# Mainboard_Geneva_Interface.net
KiCad netlist of a schematic drawn in Altium Designer
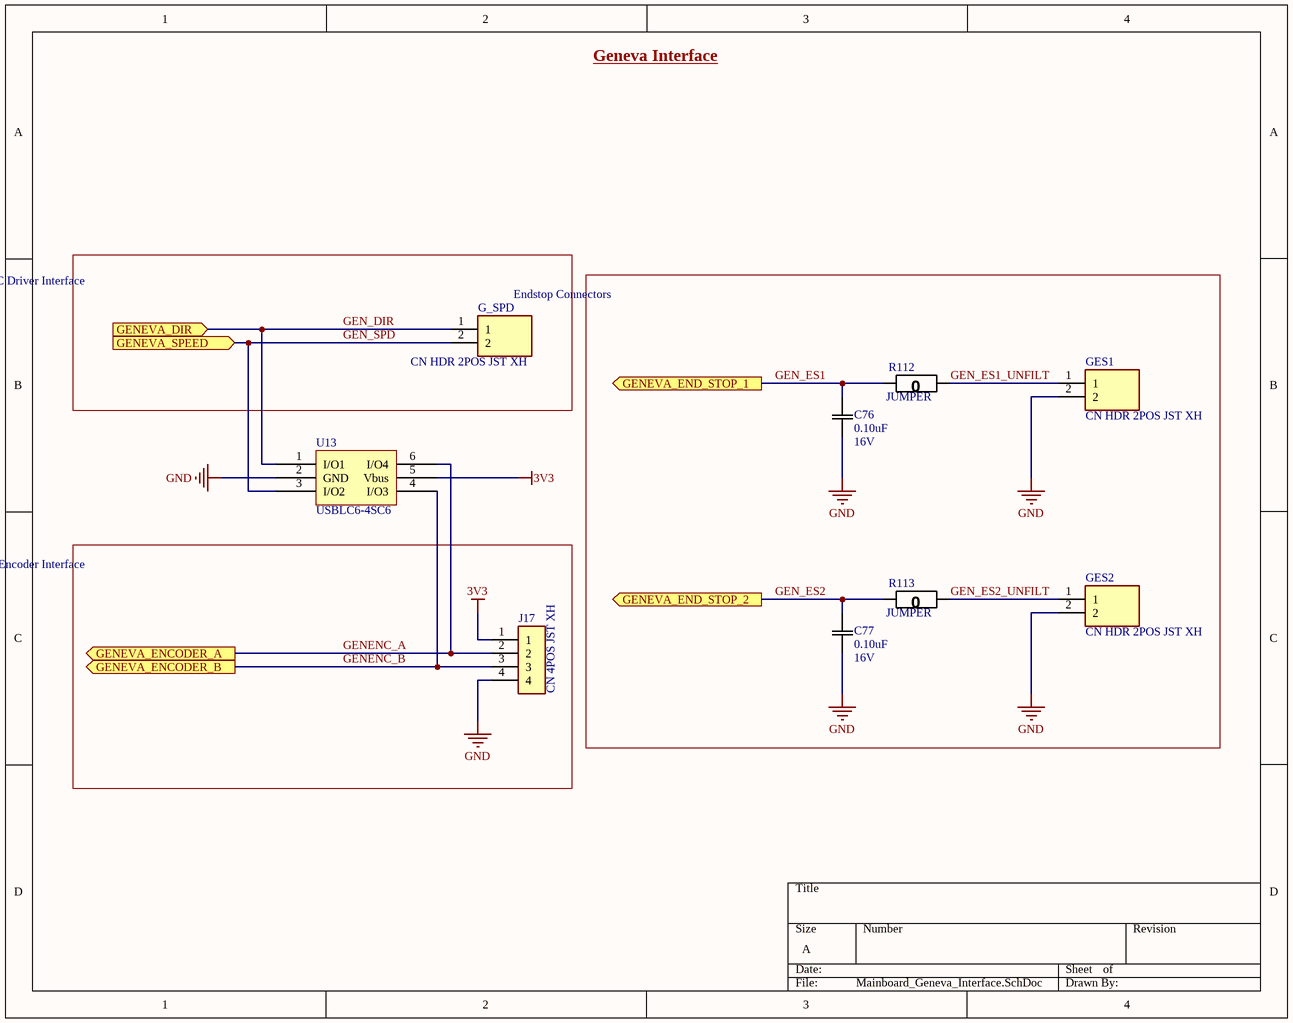
[diagram p0: Mainboard_Geneva_Interface.SchDoc]

(export (version "E")
  (design (tool "Eeschema 10.0.6"))
  (components
    (comp (ref "C76")
      (value "0.10uF")
      (footprint "0603")
      (description "CAP CER 0.10UF 16V X5R 0603/0805")
      (fields (field (name "TOLERANCE") "10%") (field (name "RATING") "16V"))
      (libsource (lib "AltiumLibraries") (part "CAP 0.10uF 16V"))
    )
    (comp (ref "C77")
      (value "0.10uF")
      (footprint "0603")
      (description "CAP CER 0.10UF 16V X5R 0603/0805")
      (fields (field (name "TOLERANCE") "10%") (field (name "RATING") "16V"))
      (libsource (lib "AltiumLibraries") (part "CAP 0.10uF 16V"))
    )
    (comp (ref "GES1")
      (value "CN HDR 2POS JST XH")
      (footprint "JST_B2B-XH-A(LF)(SN)")
      (description "Connector Header Through Hole 2 position 0.098 _2.50mm_\r\nJST XH")
      (fields (field (name "MP") "B2B-XH-A_LF__SN_") (field (name "MF") "JST Sales"))
      (libsource (lib "AltiumLibraries") (part "CN HDR 2POS JST XH"))
    )
    (comp (ref "GES2")
      (value "CN HDR 2POS JST XH")
      (footprint "JST_B2B-XH-A(LF)(SN)")
      (description "Connector Header Through Hole 2 position 0.098 _2.50mm_\r\nJST XH")
      (fields (field (name "MP") "B2B-XH-A_LF__SN_") (field (name "MF") "JST Sales"))
      (libsource (lib "AltiumLibraries") (part "CN HDR 2POS JST XH"))
    )
    (comp (ref "G_SPD")
      (value "CN HDR 2POS JST XH")
      (footprint "JST_B2B-XH-A(LF)(SN)")
      (description "Connector Header Through Hole 2 position 0.098 _2.50mm_\r\nJST XH")
      (fields (field (name "MP") "B2B-XH-A_LF__SN_") (field (name "MF") "JST Sales"))
      (libsource (lib "AltiumLibraries") (part "CN HDR 2POS JST XH"))
    )
    (comp (ref "J17")
      (value "CN 4POS JST XH")
      (footprint "JST_B4B-XH-A(LF)(SN)")
      (description "Connector Header Through Hole 4 position 0.098 _2.50mm_\r\nB4B-XH-A(LF)(SN)")
      (fields (field (name "MP") "B4B-XH-A_LF__SN_") (field (name "MF") "JST Sales"))
      (libsource (lib "AltiumLibraries") (part "CN 4POS JST XH"))
    )
    (comp (ref "R112")
      (value "JUMPER")
      (footprint "0603")
      (description "RES SMD 0 OHM JUMPER GENERIC 0805")
      (libsource (lib "AltiumLibraries") (part "RES 0 JUMPER"))
    )
    (comp (ref "R113")
      (value "JUMPER")
      (footprint "0603")
      (description "RES SMD 0 OHM JUMPER GENERIC 0805")
      (libsource (lib "AltiumLibraries") (part "RES 0 JUMPER"))
    )
    (comp (ref "U13")
      (value "USBLC6-4SC6")
      (footprint "SOT23-6L")
      (libsource (lib "AltiumLibraries") (part "USBLC6-4SC6"))
    )
  )
  (nets
    (net (code "1") (name "/GENENC_A") (class "Default")
      (node (ref "J17") (pin "2") (pinfunction "2_2") (pintype "passive"))
      (node (ref "U13") (pin "6") (pinfunction "I/O4_6") (pintype "passive"))
    )
    (net (code "2") (name "/GENENC_B") (class "Default")
      (node (ref "J17") (pin "3") (pinfunction "3_3") (pintype "passive"))
      (node (ref "U13") (pin "4") (pinfunction "I/O3_4") (pintype "passive"))
    )
    (net (code "3") (name "/GEN_DIR") (class "Default")
      (node (ref "G_SPD") (pin "1") (pinfunction "1_1") (pintype "passive"))
      (node (ref "U13") (pin "1") (pinfunction "I/O1_1") (pintype "passive"))
    )
    (net (code "4") (name "/GEN_ES1") (class "Default")
      (node (ref "C76") (pin "1") (pinfunction "C1_1") (pintype "passive"))
      (node (ref "R112") (pin "2") (pinfunction "R2_2") (pintype "passive"))
    )
    (net (code "5") (name "/GEN_ES1_UNFILT") (class "Default")
      (node (ref "GES1") (pin "1") (pinfunction "1_1") (pintype "passive"))
      (node (ref "R112") (pin "1") (pinfunction "R1_1") (pintype "passive"))
    )
    (net (code "6") (name "/GEN_ES2") (class "Default")
      (node (ref "C77") (pin "1") (pinfunction "C1_1") (pintype "passive"))
      (node (ref "R113") (pin "2") (pinfunction "R2_2") (pintype "passive"))
    )
    (net (code "7") (name "/GEN_ES2_UNFILT") (class "Default")
      (node (ref "GES2") (pin "1") (pinfunction "1_1") (pintype "passive"))
      (node (ref "R113") (pin "1") (pinfunction "R1_1") (pintype "passive"))
    )
    (net (code "8") (name "/GEN_SPD") (class "Default")
      (node (ref "G_SPD") (pin "2") (pinfunction "2_2") (pintype "passive"))
      (node (ref "U13") (pin "3") (pinfunction "I/O2_3") (pintype "passive"))
    )
    (net (code "9") (name "3V3") (class "Default")
      (node (ref "J17") (pin "1") (pinfunction "1_1") (pintype "passive"))
      (node (ref "U13") (pin "5") (pinfunction "Vbus_5") (pintype "passive"))
    )
    (net (code "10") (name "GND") (class "Default")
      (node (ref "C76") (pin "2") (pinfunction "C2_2") (pintype "passive"))
      (node (ref "C77") (pin "2") (pinfunction "C2_2") (pintype "passive"))
      (node (ref "GES1") (pin "2") (pinfunction "2_2") (pintype "passive"))
      (node (ref "GES2") (pin "2") (pinfunction "2_2") (pintype "passive"))
      (node (ref "J17") (pin "4") (pinfunction "4_4") (pintype "passive"))
      (node (ref "U13") (pin "2") (pinfunction "GND_2") (pintype "passive"))
    )
  )
)
